# Simulador_Sensor_Hall.net
KiCad netlist of a schematic drawn in EAGLE
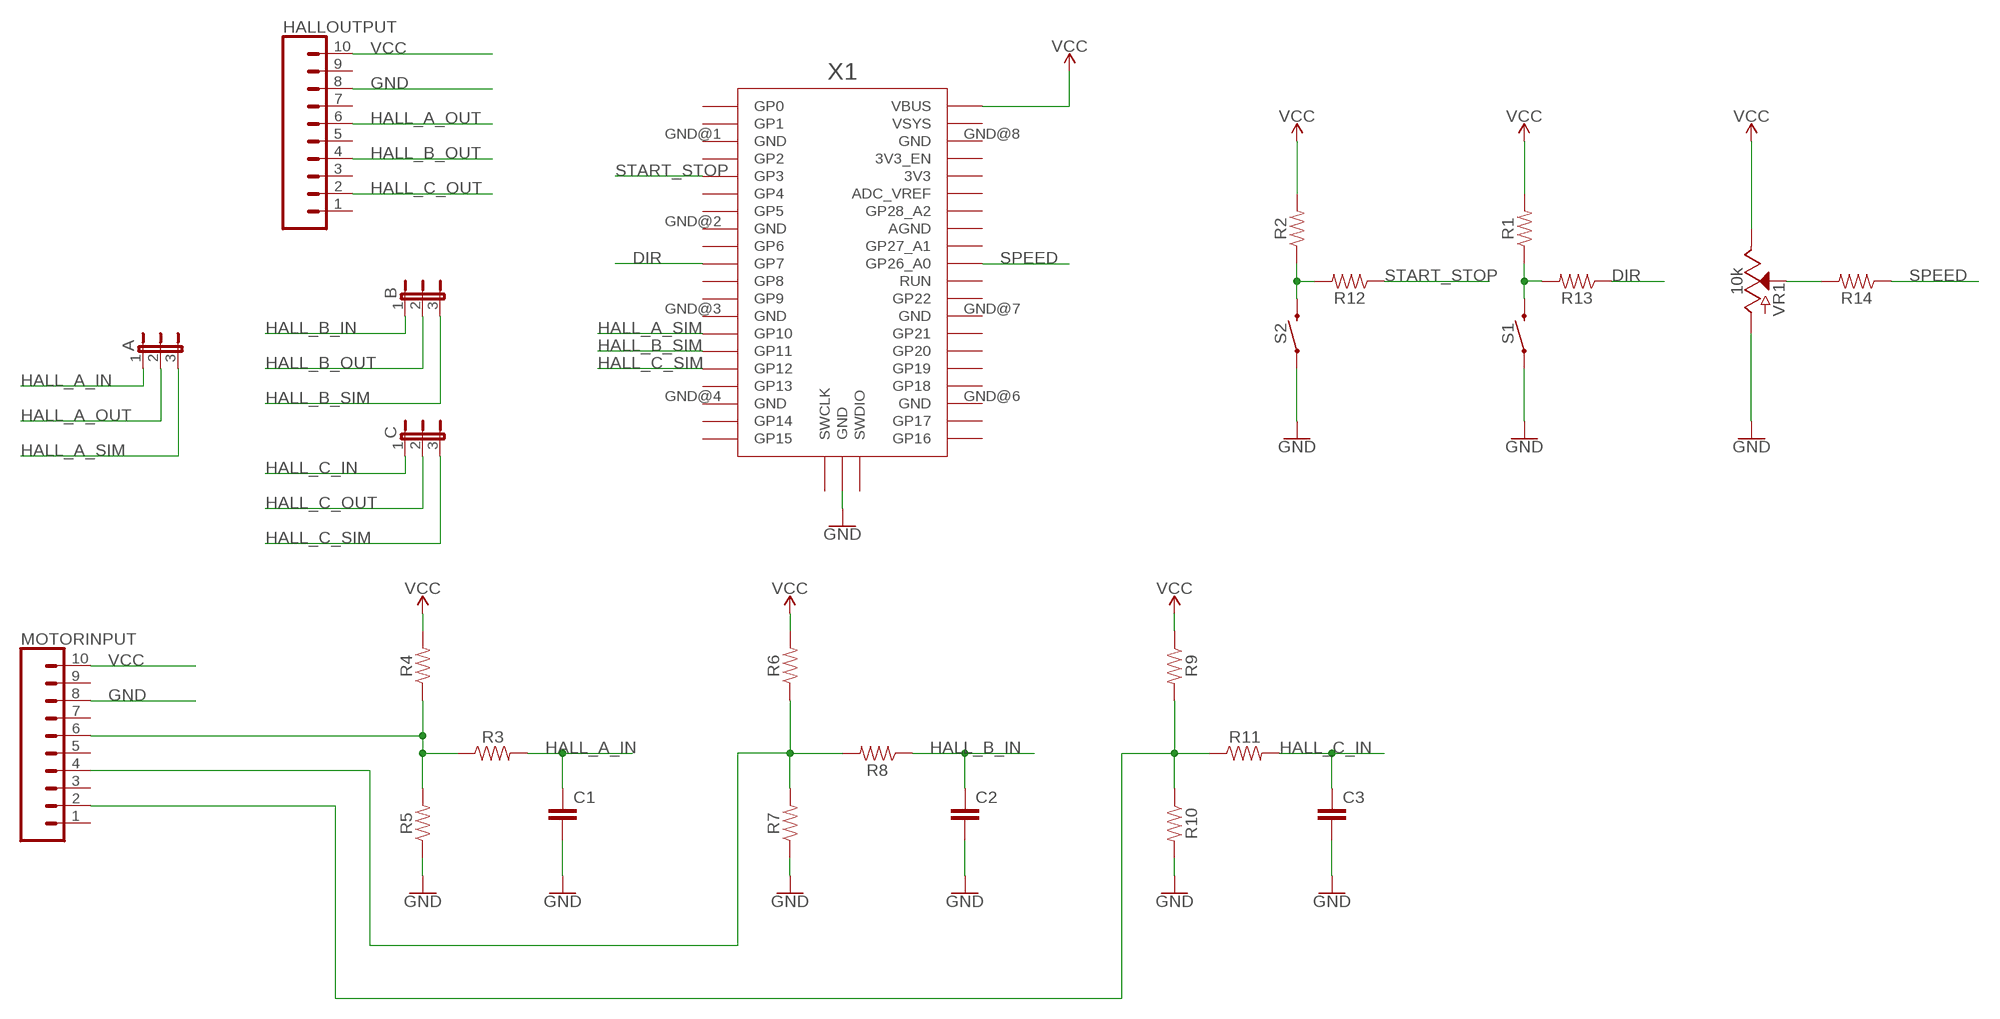
[diagram p0: schematic, sheet 1]

(export (version "E")
  (design (tool "Eeschema 10.0.6"))
  (components
    (comp (ref "A")
      (value "JP2E")
      (footprint "eagle-import:JP2")
      (libsource (lib "eagle-import") (part "JP2E"))
    )
    (comp (ref "B")
      (value "JP2E")
      (footprint "eagle-import:JP2")
      (libsource (lib "eagle-import") (part "JP2E"))
    )
    (comp (ref "C")
      (value "JP2E")
      (footprint "eagle-import:JP2")
      (libsource (lib "eagle-import") (part "JP2E"))
    )
    (comp (ref "C1")
      (value "C-EUC0805K")
      (footprint "eagle-import:C0805K")
      (libsource (lib "eagle-import") (part "C-EUC0805K"))
    )
    (comp (ref "C2")
      (value "C-EUC0805K")
      (footprint "eagle-import:C0805K")
      (libsource (lib "eagle-import") (part "C-EUC0805K"))
    )
    (comp (ref "C3")
      (value "C-EUC0805K")
      (footprint "eagle-import:C0805K")
      (libsource (lib "eagle-import") (part "C-EUC0805K"))
    )
    (comp (ref "HALLOUTPUT")
      (value "CONN_10\"")
      (footprint "eagle-import:1X10")
      (libsource (lib "eagle-import") (part "CONN_10{dblquote}"))
    )
    (comp (ref "MOTORINPUT")
      (value "CONN_10\"")
      (footprint "eagle-import:1X10")
      (libsource (lib "eagle-import") (part "CONN_10{dblquote}"))
    )
    (comp (ref "R1")
      (value "RESISTOR0805")
      (footprint "eagle-import:0805")
      (libsource (lib "eagle-import") (part "RESISTOR0805"))
    )
    (comp (ref "R2")
      (value "RESISTOR0805")
      (footprint "eagle-import:0805")
      (libsource (lib "eagle-import") (part "RESISTOR0805"))
    )
    (comp (ref "R3")
      (value "RESISTOR0805")
      (footprint "eagle-import:0805")
      (libsource (lib "eagle-import") (part "RESISTOR0805"))
    )
    (comp (ref "R4")
      (value "RESISTOR0805")
      (footprint "eagle-import:0805")
      (libsource (lib "eagle-import") (part "RESISTOR0805"))
    )
    (comp (ref "R5")
      (value "RESISTOR0805")
      (footprint "eagle-import:0805")
      (libsource (lib "eagle-import") (part "RESISTOR0805"))
    )
    (comp (ref "R6")
      (value "RESISTOR0805")
      (footprint "eagle-import:0805")
      (libsource (lib "eagle-import") (part "RESISTOR0805"))
    )
    (comp (ref "R7")
      (value "RESISTOR0805")
      (footprint "eagle-import:0805")
      (libsource (lib "eagle-import") (part "RESISTOR0805"))
    )
    (comp (ref "R8")
      (value "RESISTOR0805")
      (footprint "eagle-import:0805")
      (libsource (lib "eagle-import") (part "RESISTOR0805"))
    )
    (comp (ref "R9")
      (value "RESISTOR0805")
      (footprint "eagle-import:0805")
      (libsource (lib "eagle-import") (part "RESISTOR0805"))
    )
    (comp (ref "R10")
      (value "RESISTOR0805")
      (footprint "eagle-import:0805")
      (libsource (lib "eagle-import") (part "RESISTOR0805"))
    )
    (comp (ref "R11")
      (value "RESISTOR0805")
      (footprint "eagle-import:0805")
      (libsource (lib "eagle-import") (part "RESISTOR0805"))
    )
    (comp (ref "R12")
      (value "RESISTOR0805")
      (footprint "eagle-import:0805")
      (libsource (lib "eagle-import") (part "RESISTOR0805"))
    )
    (comp (ref "R13")
      (value "RESISTOR0805")
      (footprint "eagle-import:0805")
      (libsource (lib "eagle-import") (part "RESISTOR0805"))
    )
    (comp (ref "R14")
      (value "RESISTOR0805")
      (footprint "eagle-import:0805")
      (libsource (lib "eagle-import") (part "RESISTOR0805"))
    )
    (comp (ref "S1")
      (value "MOMENTARY-SWITCH-SPST-SMD-6.2MM-TALL")
      (footprint "eagle-import:TACTILE_SWITCH_SMD_6.2MM_TALL")
      (libsource (lib "eagle-import") (part "MOMENTARY-SWITCH-SPST-SMD-6.2MM-TALL"))
    )
    (comp (ref "S2")
      (value "MOMENTARY-SWITCH-SPST-SMD-6.2MM-TALL")
      (footprint "eagle-import:TACTILE_SWITCH_SMD_6.2MM_TALL")
      (libsource (lib "eagle-import") (part "MOMENTARY-SWITCH-SPST-SMD-6.2MM-TALL"))
    )
    (comp (ref "VR1")
      (value "10k")
      (footprint "eagle-import:POT-PTH-ALPS")
      (libsource (lib "eagle-import") (part "POTENTIOMETER-PTH-9MM-1/20W-20%"))
    )
    (comp (ref "X1")
      (value "RPI_PICO_IG-TH")
      (footprint "eagle-import:RPI_PICO_TH")
      (libsource (lib "eagle-import") (part "RPI_PICO_IG-TH"))
    )
  )
  (nets
    (net (code "1") (name "/DIR") (class "Default")
      (node (ref "R13") (pin "1") (pinfunction "1_1") (pintype "passive"))
      (node (ref "X1") (pin "GP7") (pinfunction "GP7_GP7") (pintype "bidirectional"))
    )
    (net (code "2") (name "/HALL_A_IN") (class "Default")
      (node (ref "A") (pin "1") (pinfunction "1_1") (pintype "passive"))
      (node (ref "C1") (pin "1") (pinfunction "1_1") (pintype "passive"))
      (node (ref "R3") (pin "2") (pinfunction "2_2") (pintype "passive"))
    )
    (net (code "3") (name "/HALL_A_OUT") (class "Default")
      (node (ref "A") (pin "2") (pinfunction "2_2") (pintype "passive"))
      (node (ref "HALLOUTPUT") (pin "6") (pinfunction "6_6") (pintype "passive"))
    )
    (net (code "4") (name "/HALL_A_SIM") (class "Default")
      (node (ref "A") (pin "3") (pinfunction "3_3") (pintype "passive"))
      (node (ref "X1") (pin "GP10") (pinfunction "GP10_GP10") (pintype "bidirectional"))
    )
    (net (code "5") (name "/HALL_B_IN") (class "Default")
      (node (ref "B") (pin "1") (pinfunction "1_1") (pintype "passive"))
      (node (ref "C2") (pin "1") (pinfunction "1_1") (pintype "passive"))
      (node (ref "R8") (pin "1") (pinfunction "1_1") (pintype "passive"))
    )
    (net (code "6") (name "/HALL_B_OUT") (class "Default")
      (node (ref "B") (pin "2") (pinfunction "2_2") (pintype "passive"))
      (node (ref "HALLOUTPUT") (pin "4") (pinfunction "4_4") (pintype "passive"))
    )
    (net (code "7") (name "/HALL_B_SIM") (class "Default")
      (node (ref "B") (pin "3") (pinfunction "3_3") (pintype "passive"))
      (node (ref "X1") (pin "GP11") (pinfunction "GP11_GP11") (pintype "bidirectional"))
    )
    (net (code "8") (name "/HALL_C_IN") (class "Default")
      (node (ref "C") (pin "1") (pinfunction "1_1") (pintype "passive"))
      (node (ref "C3") (pin "1") (pinfunction "1_1") (pintype "passive"))
      (node (ref "R11") (pin "2") (pinfunction "2_2") (pintype "passive"))
    )
    (net (code "9") (name "/HALL_C_OUT") (class "Default")
      (node (ref "C") (pin "2") (pinfunction "2_2") (pintype "passive"))
      (node (ref "HALLOUTPUT") (pin "2") (pinfunction "2_2") (pintype "passive"))
    )
    (net (code "10") (name "/HALL_C_SIM") (class "Default")
      (node (ref "C") (pin "3") (pinfunction "3_3") (pintype "passive"))
      (node (ref "X1") (pin "GP12") (pinfunction "GP12_GP12") (pintype "bidirectional"))
    )
    (net (code "11") (name "/SPEED") (class "Default")
      (node (ref "R14") (pin "1") (pinfunction "1_1") (pintype "passive"))
      (node (ref "X1") (pin "GP26_A0") (pinfunction "GP26_A0_GP26_A0") (pintype "bidirectional"))
    )
    (net (code "12") (name "/START_STOP") (class "Default")
      (node (ref "R12") (pin "1") (pinfunction "1_1") (pintype "passive"))
      (node (ref "X1") (pin "GP3") (pinfunction "GP3_GP3") (pintype "bidirectional"))
    )
    (net (code "13") (name "GND") (class "Default")
      (node (ref "C1") (pin "2") (pinfunction "2_2") (pintype "passive"))
      (node (ref "C2") (pin "2") (pinfunction "2_2") (pintype "passive"))
      (node (ref "C3") (pin "2") (pinfunction "2_2") (pintype "passive"))
      (node (ref "HALLOUTPUT") (pin "8") (pinfunction "8_8") (pintype "passive"))
      (node (ref "MOTORINPUT") (pin "8") (pinfunction "8_8") (pintype "passive"))
      (node (ref "R10") (pin "2") (pinfunction "2_2") (pintype "passive"))
      (node (ref "R5") (pin "1") (pinfunction "1_1") (pintype "passive"))
      (node (ref "R7") (pin "1") (pinfunction "1_1") (pintype "passive"))
      (node (ref "S1") (pin "A2") (pinfunction "1_A2") (pintype "passive"))
      (node (ref "S2") (pin "A2") (pinfunction "1_A2") (pintype "passive"))
      (node (ref "VR1") (pin "P$3") (pinfunction "A_P$3") (pintype "passive"))
      (node (ref "X1") (pin "GND@5") (pinfunction "GND_GND@5") (pintype "bidirectional"))
    )
    (net (code "14") (name "Net-(MOTORINPUT-Pad2)") (class "Default")
      (node (ref "MOTORINPUT") (pin "2") (pinfunction "2_2") (pintype "passive"))
      (node (ref "R10") (pin "1") (pinfunction "1_1") (pintype "passive"))
      (node (ref "R11") (pin "1") (pinfunction "1_1") (pintype "passive"))
      (node (ref "R9") (pin "2") (pinfunction "2_2") (pintype "passive"))
    )
    (net (code "15") (name "Net-(MOTORINPUT-Pad4)") (class "Default")
      (node (ref "MOTORINPUT") (pin "4") (pinfunction "4_4") (pintype "passive"))
      (node (ref "R6") (pin "1") (pinfunction "1_1") (pintype "passive"))
      (node (ref "R7") (pin "2") (pinfunction "2_2") (pintype "passive"))
      (node (ref "R8") (pin "2") (pinfunction "2_2") (pintype "passive"))
    )
    (net (code "16") (name "Net-(MOTORINPUT-Pad6)") (class "Default")
      (node (ref "MOTORINPUT") (pin "6") (pinfunction "6_6") (pintype "passive"))
      (node (ref "R3") (pin "1") (pinfunction "1_1") (pintype "passive"))
      (node (ref "R4") (pin "1") (pinfunction "1_1") (pintype "passive"))
      (node (ref "R5") (pin "2") (pinfunction "2_2") (pintype "passive"))
    )
    (net (code "17") (name "Net-(S1-2)") (class "Default")
      (node (ref "R1") (pin "1") (pinfunction "1_1") (pintype "passive"))
      (node (ref "R13") (pin "2") (pinfunction "2_2") (pintype "passive"))
      (node (ref "S1") (pin "B2") (pinfunction "2_B2") (pintype "passive"))
    )
    (net (code "18") (name "Net-(S2-2)") (class "Default")
      (node (ref "R12") (pin "2") (pinfunction "2_2") (pintype "passive"))
      (node (ref "R2") (pin "1") (pinfunction "1_1") (pintype "passive"))
      (node (ref "S2") (pin "B2") (pinfunction "2_B2") (pintype "passive"))
    )
    (net (code "19") (name "Net-(VR1-S)") (class "Default")
      (node (ref "R14") (pin "2") (pinfunction "2_2") (pintype "passive"))
      (node (ref "VR1") (pin "P$2") (pinfunction "S_P$2") (pintype "passive"))
    )
    (net (code "20") (name "VCC") (class "Default")
      (node (ref "HALLOUTPUT") (pin "10") (pinfunction "10_10") (pintype "passive"))
      (node (ref "MOTORINPUT") (pin "10") (pinfunction "10_10") (pintype "passive"))
      (node (ref "R1") (pin "2") (pinfunction "2_2") (pintype "passive"))
      (node (ref "R2") (pin "2") (pinfunction "2_2") (pintype "passive"))
      (node (ref "R4") (pin "2") (pinfunction "2_2") (pintype "passive"))
      (node (ref "R6") (pin "2") (pinfunction "2_2") (pintype "passive"))
      (node (ref "R9") (pin "1") (pinfunction "1_1") (pintype "passive"))
      (node (ref "VR1") (pin "P$1") (pinfunction "E_P$1") (pintype "passive"))
      (node (ref "X1") (pin "VBUS") (pinfunction "VBUS_VBUS") (pintype "bidirectional"))
    )
    (net (code "21") (name "unconnected-(HALLOUTPUT-Pad1)") (class "Default")
      (node (ref "HALLOUTPUT") (pin "1") (pinfunction "1_1") (pintype "passive"))
    )
    (net (code "22") (name "unconnected-(HALLOUTPUT-Pad3)") (class "Default")
      (node (ref "HALLOUTPUT") (pin "3") (pinfunction "3_3") (pintype "passive"))
    )
    (net (code "23") (name "unconnected-(HALLOUTPUT-Pad5)") (class "Default")
      (node (ref "HALLOUTPUT") (pin "5") (pinfunction "5_5") (pintype "passive"))
    )
    (net (code "24") (name "unconnected-(HALLOUTPUT-Pad7)") (class "Default")
      (node (ref "HALLOUTPUT") (pin "7") (pinfunction "7_7") (pintype "passive"))
    )
    (net (code "25") (name "unconnected-(HALLOUTPUT-Pad9)") (class "Default")
      (node (ref "HALLOUTPUT") (pin "9") (pinfunction "9_9") (pintype "passive"))
    )
    (net (code "26") (name "unconnected-(MOTORINPUT-Pad1)") (class "Default")
      (node (ref "MOTORINPUT") (pin "1") (pinfunction "1_1") (pintype "passive"))
    )
    (net (code "27") (name "unconnected-(MOTORINPUT-Pad3)") (class "Default")
      (node (ref "MOTORINPUT") (pin "3") (pinfunction "3_3") (pintype "passive"))
    )
    (net (code "28") (name "unconnected-(MOTORINPUT-Pad5)") (class "Default")
      (node (ref "MOTORINPUT") (pin "5") (pinfunction "5_5") (pintype "passive"))
    )
    (net (code "29") (name "unconnected-(MOTORINPUT-Pad7)") (class "Default")
      (node (ref "MOTORINPUT") (pin "7") (pinfunction "7_7") (pintype "passive"))
    )
    (net (code "30") (name "unconnected-(MOTORINPUT-Pad9)") (class "Default")
      (node (ref "MOTORINPUT") (pin "9") (pinfunction "9_9") (pintype "passive"))
    )
    (net (code "31") (name "unconnected-(X1-GND-PadGND@1)") (class "Default")
      (node (ref "X1") (pin "GND@1") (pinfunction "GND_GND@1") (pintype "bidirectional"))
    )
    (net (code "32") (name "unconnected-(X1-GND-PadGND@2)") (class "Default")
      (node (ref "X1") (pin "GND@2") (pinfunction "GND_GND@2") (pintype "bidirectional"))
    )
    (net (code "33") (name "unconnected-(X1-GND-PadGND@3)") (class "Default")
      (node (ref "X1") (pin "GND@3") (pinfunction "GND_GND@3") (pintype "bidirectional"))
    )
    (net (code "34") (name "unconnected-(X1-GND-PadGND@4)") (class "Default")
      (node (ref "X1") (pin "GND@4") (pinfunction "GND_GND@4") (pintype "bidirectional"))
    )
    (net (code "35") (name "unconnected-(X1-GND-PadGND@6)") (class "Default")
      (node (ref "X1") (pin "GND@6") (pinfunction "GND_GND@6") (pintype "bidirectional"))
    )
    (net (code "36") (name "unconnected-(X1-GND-PadGND@7)") (class "Default")
      (node (ref "X1") (pin "GND@7") (pinfunction "GND_GND@7") (pintype "bidirectional"))
    )
    (net (code "37") (name "unconnected-(X1-GND-PadGND@8)") (class "Default")
      (node (ref "X1") (pin "GND@8") (pinfunction "GND_GND@8") (pintype "bidirectional"))
    )
    (net (code "38") (name "unconnected-(X1-Pad3V3)") (class "Default")
      (node (ref "X1") (pin "3V3") (pinfunction "3V3_3V3") (pintype "bidirectional"))
    )
    (net (code "39") (name "unconnected-(X1-Pad3V3_EN)") (class "Default")
      (node (ref "X1") (pin "3V3_EN") (pinfunction "3V3_EN_3V3_EN") (pintype "bidirectional"))
    )
    (net (code "40") (name "unconnected-(X1-PadADC_VREF)") (class "Default")
      (node (ref "X1") (pin "ADC_VREF") (pinfunction "ADC_VREF_ADC_VREF") (pintype "bidirectional"))
    )
    (net (code "41") (name "unconnected-(X1-PadAGND)") (class "Default")
      (node (ref "X1") (pin "AGND") (pinfunction "AGND_AGND") (pintype "bidirectional"))
    )
    (net (code "42") (name "unconnected-(X1-PadGP0)") (class "Default")
      (node (ref "X1") (pin "GP0") (pinfunction "GP0_GP0") (pintype "bidirectional"))
    )
    (net (code "43") (name "unconnected-(X1-PadGP1)") (class "Default")
      (node (ref "X1") (pin "GP1") (pinfunction "GP1_GP1") (pintype "bidirectional"))
    )
    (net (code "44") (name "unconnected-(X1-PadGP2)") (class "Default")
      (node (ref "X1") (pin "GP2") (pinfunction "GP2_GP2") (pintype "bidirectional"))
    )
    (net (code "45") (name "unconnected-(X1-PadGP4)") (class "Default")
      (node (ref "X1") (pin "GP4") (pinfunction "GP4_GP4") (pintype "bidirectional"))
    )
    (net (code "46") (name "unconnected-(X1-PadGP5)") (class "Default")
      (node (ref "X1") (pin "GP5") (pinfunction "GP5_GP5") (pintype "bidirectional"))
    )
    (net (code "47") (name "unconnected-(X1-PadGP6)") (class "Default")
      (node (ref "X1") (pin "GP6") (pinfunction "GP6_GP6") (pintype "bidirectional"))
    )
    (net (code "48") (name "unconnected-(X1-PadGP8)") (class "Default")
      (node (ref "X1") (pin "GP8") (pinfunction "GP8_GP8") (pintype "bidirectional"))
    )
    (net (code "49") (name "unconnected-(X1-PadGP9)") (class "Default")
      (node (ref "X1") (pin "GP9") (pinfunction "GP9_GP9") (pintype "bidirectional"))
    )
    (net (code "50") (name "unconnected-(X1-PadGP13)") (class "Default")
      (node (ref "X1") (pin "GP13") (pinfunction "GP13_GP13") (pintype "bidirectional"))
    )
    (net (code "51") (name "unconnected-(X1-PadGP14)") (class "Default")
      (node (ref "X1") (pin "GP14") (pinfunction "GP14_GP14") (pintype "bidirectional"))
    )
    (net (code "52") (name "unconnected-(X1-PadGP15)") (class "Default")
      (node (ref "X1") (pin "GP15") (pinfunction "GP15_GP15") (pintype "bidirectional"))
    )
    (net (code "53") (name "unconnected-(X1-PadGP16)") (class "Default")
      (node (ref "X1") (pin "GP16") (pinfunction "GP16_GP16") (pintype "bidirectional"))
    )
    (net (code "54") (name "unconnected-(X1-PadGP17)") (class "Default")
      (node (ref "X1") (pin "GP17") (pinfunction "GP17_GP17") (pintype "bidirectional"))
    )
    (net (code "55") (name "unconnected-(X1-PadGP18)") (class "Default")
      (node (ref "X1") (pin "GP18") (pinfunction "GP18_GP18") (pintype "bidirectional"))
    )
    (net (code "56") (name "unconnected-(X1-PadGP19)") (class "Default")
      (node (ref "X1") (pin "GP19") (pinfunction "GP19_GP19") (pintype "bidirectional"))
    )
    (net (code "57") (name "unconnected-(X1-PadGP20)") (class "Default")
      (node (ref "X1") (pin "GP20") (pinfunction "GP20_GP20") (pintype "bidirectional"))
    )
    (net (code "58") (name "unconnected-(X1-PadGP21)") (class "Default")
      (node (ref "X1") (pin "GP21") (pinfunction "GP21_GP21") (pintype "bidirectional"))
    )
    (net (code "59") (name "unconnected-(X1-PadGP22)") (class "Default")
      (node (ref "X1") (pin "GP22") (pinfunction "GP22_GP22") (pintype "bidirectional"))
    )
    (net (code "60") (name "unconnected-(X1-PadGP27_A1)") (class "Default")
      (node (ref "X1") (pin "GP27_A1") (pinfunction "GP27_A1_GP27_A1") (pintype "bidirectional"))
    )
    (net (code "61") (name "unconnected-(X1-PadGP28_A2)") (class "Default")
      (node (ref "X1") (pin "GP28_A2") (pinfunction "GP28_A2_GP28_A2") (pintype "bidirectional"))
    )
    (net (code "62") (name "unconnected-(X1-PadRUN)") (class "Default")
      (node (ref "X1") (pin "RUN") (pinfunction "RUN_RUN") (pintype "bidirectional"))
    )
    (net (code "63") (name "unconnected-(X1-PadSWCLK)") (class "Default")
      (node (ref "X1") (pin "SWCLK") (pinfunction "SWCLK_SWCLK") (pintype "bidirectional"))
    )
    (net (code "64") (name "unconnected-(X1-PadSWDIO)") (class "Default")
      (node (ref "X1") (pin "SWDIO") (pinfunction "SWDIO_SWDIO") (pintype "bidirectional"))
    )
    (net (code "65") (name "unconnected-(X1-PadVSYS)") (class "Default")
      (node (ref "X1") (pin "VSYS") (pinfunction "VSYS_VSYS") (pintype "bidirectional"))
    )
  )
)
